# con-right-top.net
KiCad netlist of a schematic drawn in Altium Designer
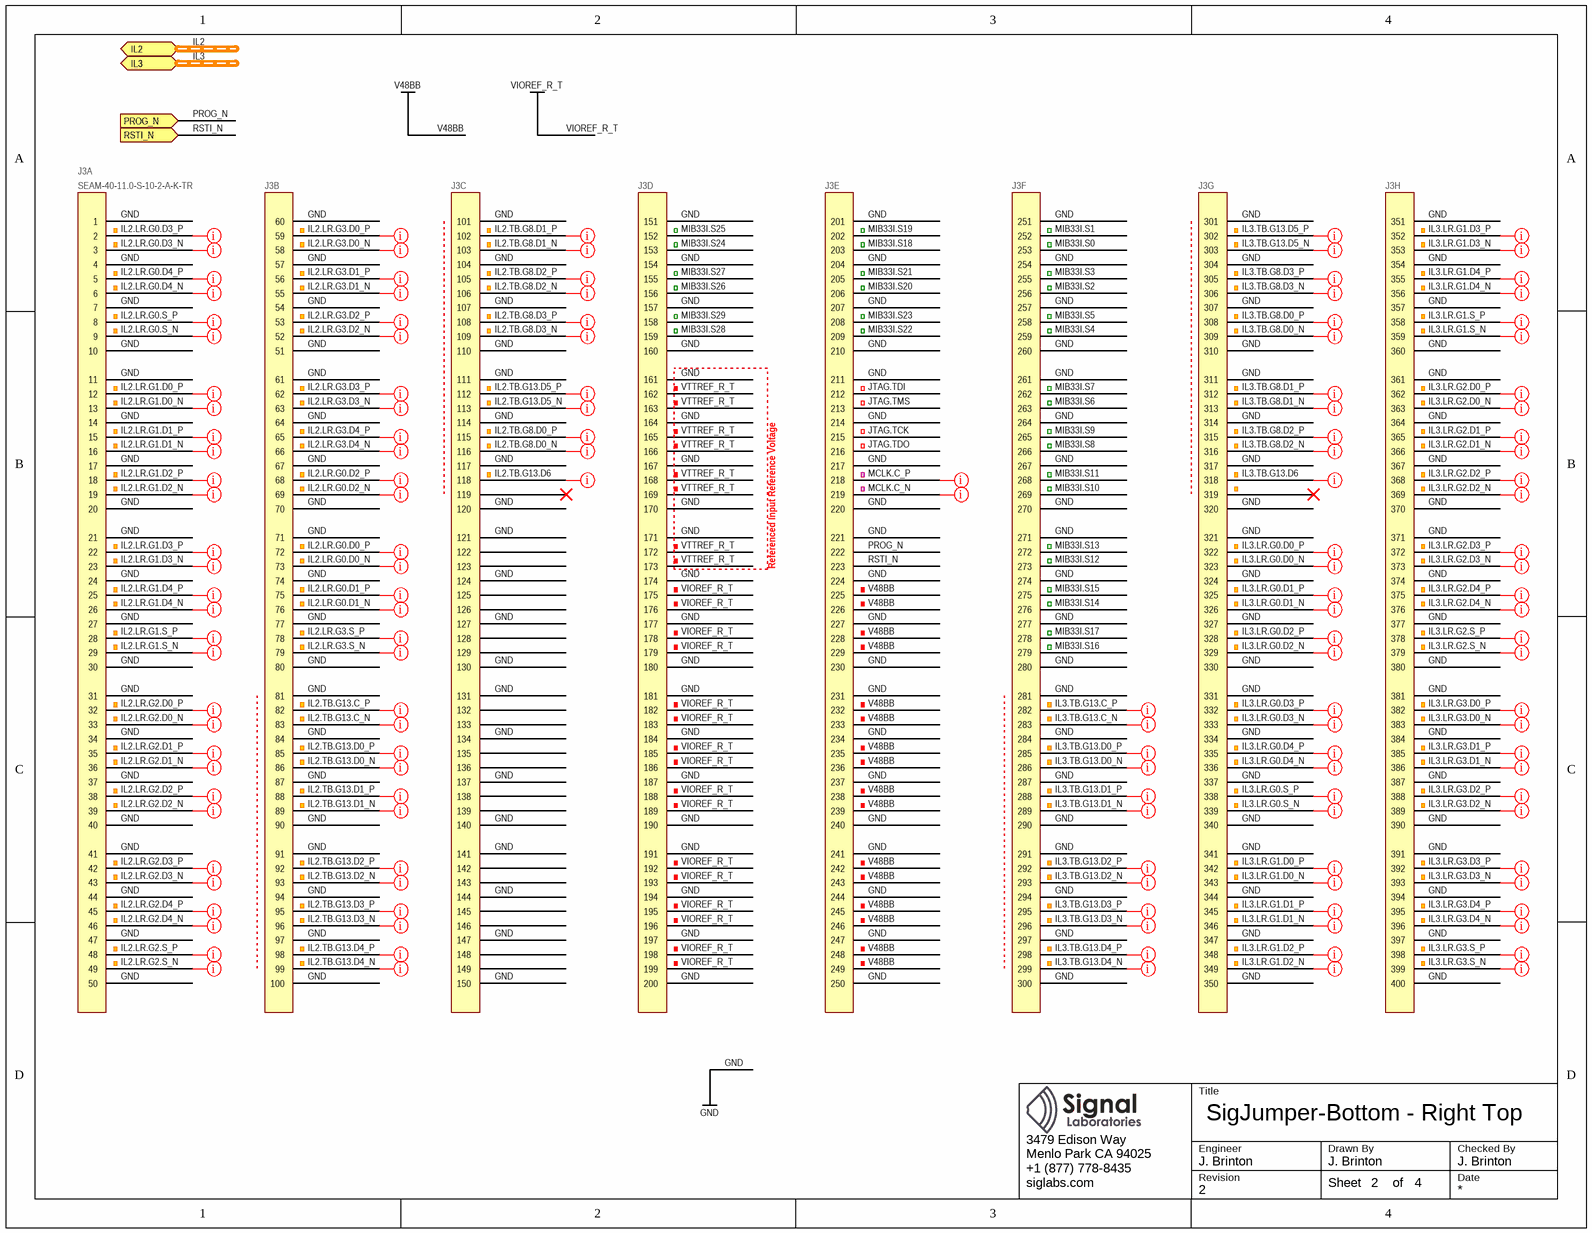
[diagram p0: con-right-top.SchDoc]

(export (version "E")
  (design (tool "Eeschema 10.0.6"))
  (components
    (comp (ref "J3")
      (value "SEAM-40-11.0-S-10-2-A-K-TR")
      (footprint "samtec:SEAM-40-11.0-S-10-2-A-K-TR")
      (description "Terminal Array Assembly, Surface Mount, 0.050\" Pitch, 400 Pins")
      (fields (field (name "MANUFACTURER") "Samtec"))
      (libsource (lib "samtec") (part "SEAM-40-11.0-S-10-2-A-K-TR"))
    )
  )
  (nets
    (net (code "3") (name "/IL2.LR.G0.D0_N") (class "Default")
      (node (ref "J3") (pin "73") (pinfunction "73_73") (pintype "passive"))
    )
    (net (code "4") (name "/IL2.LR.G0.D0_P") (class "Default")
      (node (ref "J3") (pin "72") (pinfunction "72_72") (pintype "passive"))
    )
    (net (code "5") (name "/IL2.LR.G0.D1_N") (class "Default")
      (node (ref "J3") (pin "76") (pinfunction "76_76") (pintype "passive"))
    )
    (net (code "6") (name "/IL2.LR.G0.D1_P") (class "Default")
      (node (ref "J3") (pin "75") (pinfunction "75_75") (pintype "passive"))
    )
    (net (code "7") (name "/IL2.LR.G0.D2_N") (class "Default")
      (node (ref "J3") (pin "69") (pinfunction "69_69") (pintype "passive"))
    )
    (net (code "8") (name "/IL2.LR.G0.D2_P") (class "Default")
      (node (ref "J3") (pin "68") (pinfunction "68_68") (pintype "passive"))
    )
    (net (code "9") (name "/IL2.LR.G0.D3_N") (class "Default")
      (node (ref "J3") (pin "3") (pinfunction "3_3") (pintype "passive"))
    )
    (net (code "10") (name "/IL2.LR.G0.D3_P") (class "Default")
      (node (ref "J3") (pin "2") (pinfunction "2_2") (pintype "passive"))
    )
    (net (code "11") (name "/IL2.LR.G0.D4_N") (class "Default")
      (node (ref "J3") (pin "6") (pinfunction "6_6") (pintype "passive"))
    )
    (net (code "12") (name "/IL2.LR.G0.D4_P") (class "Default")
      (node (ref "J3") (pin "5") (pinfunction "5_5") (pintype "passive"))
    )
    (net (code "13") (name "/IL2.LR.G0.S_N") (class "Default")
      (node (ref "J3") (pin "9") (pinfunction "9_9") (pintype "passive"))
    )
    (net (code "14") (name "/IL2.LR.G0.S_P") (class "Default")
      (node (ref "J3") (pin "8") (pinfunction "8_8") (pintype "passive"))
    )
    (net (code "15") (name "/IL2.LR.G1.D0_N") (class "Default")
      (node (ref "J3") (pin "13") (pinfunction "13_13") (pintype "passive"))
    )
    (net (code "16") (name "/IL2.LR.G1.D0_P") (class "Default")
      (node (ref "J3") (pin "12") (pinfunction "12_12") (pintype "passive"))
    )
    (net (code "17") (name "/IL2.LR.G1.D1_N") (class "Default")
      (node (ref "J3") (pin "16") (pinfunction "16_16") (pintype "passive"))
    )
    (net (code "18") (name "/IL2.LR.G1.D1_P") (class "Default")
      (node (ref "J3") (pin "15") (pinfunction "15_15") (pintype "passive"))
    )
    (net (code "19") (name "/IL2.LR.G1.D2_N") (class "Default")
      (node (ref "J3") (pin "19") (pinfunction "19_19") (pintype "passive"))
    )
    (net (code "20") (name "/IL2.LR.G1.D2_P") (class "Default")
      (node (ref "J3") (pin "18") (pinfunction "18_18") (pintype "passive"))
    )
    (net (code "21") (name "/IL2.LR.G1.D3_N") (class "Default")
      (node (ref "J3") (pin "23") (pinfunction "23_23") (pintype "passive"))
    )
    (net (code "22") (name "/IL2.LR.G1.D3_P") (class "Default")
      (node (ref "J3") (pin "22") (pinfunction "22_22") (pintype "passive"))
    )
    (net (code "23") (name "/IL2.LR.G1.D4_N") (class "Default")
      (node (ref "J3") (pin "26") (pinfunction "26_26") (pintype "passive"))
    )
    (net (code "24") (name "/IL2.LR.G1.D4_P") (class "Default")
      (node (ref "J3") (pin "25") (pinfunction "25_25") (pintype "passive"))
    )
    (net (code "25") (name "/IL2.LR.G1.S_N") (class "Default")
      (node (ref "J3") (pin "29") (pinfunction "29_29") (pintype "passive"))
    )
    (net (code "26") (name "/IL2.LR.G1.S_P") (class "Default")
      (node (ref "J3") (pin "28") (pinfunction "28_28") (pintype "passive"))
    )
    (net (code "27") (name "/IL2.LR.G2.D0_N") (class "Default")
      (node (ref "J3") (pin "33") (pinfunction "33_33") (pintype "passive"))
    )
    (net (code "28") (name "/IL2.LR.G2.D0_P") (class "Default")
      (node (ref "J3") (pin "32") (pinfunction "32_32") (pintype "passive"))
    )
    (net (code "29") (name "/IL2.LR.G2.D1_N") (class "Default")
      (node (ref "J3") (pin "36") (pinfunction "36_36") (pintype "passive"))
    )
    (net (code "30") (name "/IL2.LR.G2.D1_P") (class "Default")
      (node (ref "J3") (pin "35") (pinfunction "35_35") (pintype "passive"))
    )
    (net (code "31") (name "/IL2.LR.G2.D2_N") (class "Default")
      (node (ref "J3") (pin "39") (pinfunction "39_39") (pintype "passive"))
    )
    (net (code "32") (name "/IL2.LR.G2.D2_P") (class "Default")
      (node (ref "J3") (pin "38") (pinfunction "38_38") (pintype "passive"))
    )
    (net (code "33") (name "/IL2.LR.G2.D3_N") (class "Default")
      (node (ref "J3") (pin "43") (pinfunction "43_43") (pintype "passive"))
    )
    (net (code "34") (name "/IL2.LR.G2.D3_P") (class "Default")
      (node (ref "J3") (pin "42") (pinfunction "42_42") (pintype "passive"))
    )
    (net (code "35") (name "/IL2.LR.G2.D4_N") (class "Default")
      (node (ref "J3") (pin "46") (pinfunction "46_46") (pintype "passive"))
    )
    (net (code "36") (name "/IL2.LR.G2.D4_P") (class "Default")
      (node (ref "J3") (pin "45") (pinfunction "45_45") (pintype "passive"))
    )
    (net (code "37") (name "/IL2.LR.G2.S_N") (class "Default")
      (node (ref "J3") (pin "49") (pinfunction "49_49") (pintype "passive"))
    )
    (net (code "38") (name "/IL2.LR.G2.S_P") (class "Default")
      (node (ref "J3") (pin "48") (pinfunction "48_48") (pintype "passive"))
    )
    (net (code "39") (name "/IL2.LR.G3.D0_N") (class "Default")
      (node (ref "J3") (pin "58") (pinfunction "58_58") (pintype "passive"))
    )
    (net (code "40") (name "/IL2.LR.G3.D0_P") (class "Default")
      (node (ref "J3") (pin "59") (pinfunction "59_59") (pintype "passive"))
    )
    (net (code "41") (name "/IL2.LR.G3.D1_N") (class "Default")
      (node (ref "J3") (pin "55") (pinfunction "55_55") (pintype "passive"))
    )
    (net (code "42") (name "/IL2.LR.G3.D1_P") (class "Default")
      (node (ref "J3") (pin "56") (pinfunction "56_56") (pintype "passive"))
    )
    (net (code "43") (name "/IL2.LR.G3.D2_N") (class "Default")
      (node (ref "J3") (pin "52") (pinfunction "52_52") (pintype "passive"))
    )
    (net (code "44") (name "/IL2.LR.G3.D2_P") (class "Default")
      (node (ref "J3") (pin "53") (pinfunction "53_53") (pintype "passive"))
    )
    (net (code "45") (name "/IL2.LR.G3.D3_N") (class "Default")
      (node (ref "J3") (pin "63") (pinfunction "63_63") (pintype "passive"))
    )
    (net (code "46") (name "/IL2.LR.G3.D3_P") (class "Default")
      (node (ref "J3") (pin "62") (pinfunction "62_62") (pintype "passive"))
    )
    (net (code "47") (name "/IL2.LR.G3.D4_N") (class "Default")
      (node (ref "J3") (pin "66") (pinfunction "66_66") (pintype "passive"))
    )
    (net (code "48") (name "/IL2.LR.G3.D4_P") (class "Default")
      (node (ref "J3") (pin "65") (pinfunction "65_65") (pintype "passive"))
    )
    (net (code "49") (name "/IL2.LR.G3.S_N") (class "Default")
      (node (ref "J3") (pin "79") (pinfunction "79_79") (pintype "passive"))
    )
    (net (code "50") (name "/IL2.LR.G3.S_P") (class "Default")
      (node (ref "J3") (pin "78") (pinfunction "78_78") (pintype "passive"))
    )
    (net (code "51") (name "/IL2.TB.G8.D0_N") (class "Default")
      (node (ref "J3") (pin "116") (pinfunction "116_116") (pintype "passive"))
    )
    (net (code "52") (name "/IL2.TB.G8.D0_P") (class "Default")
      (node (ref "J3") (pin "115") (pinfunction "115_115") (pintype "passive"))
    )
    (net (code "53") (name "/IL2.TB.G8.D1_N") (class "Default")
      (node (ref "J3") (pin "103") (pinfunction "103_103") (pintype "passive"))
    )
    (net (code "54") (name "/IL2.TB.G8.D1_P") (class "Default")
      (node (ref "J3") (pin "102") (pinfunction "102_102") (pintype "passive"))
    )
    (net (code "55") (name "/IL2.TB.G8.D2_N") (class "Default")
      (node (ref "J3") (pin "106") (pinfunction "106_106") (pintype "passive"))
    )
    (net (code "56") (name "/IL2.TB.G8.D2_P") (class "Default")
      (node (ref "J3") (pin "105") (pinfunction "105_105") (pintype "passive"))
    )
    (net (code "57") (name "/IL2.TB.G8.D3_N") (class "Default")
      (node (ref "J3") (pin "109") (pinfunction "109_109") (pintype "passive"))
    )
    (net (code "58") (name "/IL2.TB.G8.D3_P") (class "Default")
      (node (ref "J3") (pin "108") (pinfunction "108_108") (pintype "passive"))
    )
    (net (code "59") (name "/IL2.TB.G13.C_N") (class "Default")
      (node (ref "J3") (pin "83") (pinfunction "83_83") (pintype "passive"))
    )
    (net (code "60") (name "/IL2.TB.G13.C_P") (class "Default")
      (node (ref "J3") (pin "82") (pinfunction "82_82") (pintype "passive"))
    )
    (net (code "61") (name "/IL2.TB.G13.D0_N") (class "Default")
      (node (ref "J3") (pin "86") (pinfunction "86_86") (pintype "passive"))
    )
    (net (code "62") (name "/IL2.TB.G13.D0_P") (class "Default")
      (node (ref "J3") (pin "85") (pinfunction "85_85") (pintype "passive"))
    )
    (net (code "63") (name "/IL2.TB.G13.D1_N") (class "Default")
      (node (ref "J3") (pin "89") (pinfunction "89_89") (pintype "passive"))
    )
    (net (code "64") (name "/IL2.TB.G13.D1_P") (class "Default")
      (node (ref "J3") (pin "88") (pinfunction "88_88") (pintype "passive"))
    )
    (net (code "65") (name "/IL2.TB.G13.D2_N") (class "Default")
      (node (ref "J3") (pin "93") (pinfunction "93_93") (pintype "passive"))
    )
    (net (code "66") (name "/IL2.TB.G13.D2_P") (class "Default")
      (node (ref "J3") (pin "92") (pinfunction "92_92") (pintype "passive"))
    )
    (net (code "67") (name "/IL2.TB.G13.D3_N") (class "Default")
      (node (ref "J3") (pin "96") (pinfunction "96_96") (pintype "passive"))
    )
    (net (code "68") (name "/IL2.TB.G13.D3_P") (class "Default")
      (node (ref "J3") (pin "95") (pinfunction "95_95") (pintype "passive"))
    )
    (net (code "69") (name "/IL2.TB.G13.D4_N") (class "Default")
      (node (ref "J3") (pin "99") (pinfunction "99_99") (pintype "passive"))
    )
    (net (code "70") (name "/IL2.TB.G13.D4_P") (class "Default")
      (node (ref "J3") (pin "98") (pinfunction "98_98") (pintype "passive"))
    )
    (net (code "71") (name "/IL2.TB.G13.D5_N") (class "Default")
      (node (ref "J3") (pin "113") (pinfunction "113_113") (pintype "passive"))
    )
    (net (code "72") (name "/IL2.TB.G13.D5_P") (class "Default")
      (node (ref "J3") (pin "112") (pinfunction "112_112") (pintype "passive"))
    )
    (net (code "73") (name "/IL2.TB.G13.D6") (class "Default")
      (node (ref "J3") (pin "118") (pinfunction "118_118") (pintype "passive"))
    )
    (net (code "74") (name "/IL3.LR.G0.D0_N") (class "Default")
      (node (ref "J3") (pin "323") (pinfunction "323_323") (pintype "passive"))
    )
    (net (code "75") (name "/IL3.LR.G0.D0_P") (class "Default")
      (node (ref "J3") (pin "322") (pinfunction "322_322") (pintype "passive"))
    )
    (net (code "76") (name "/IL3.LR.G0.D1_N") (class "Default")
      (node (ref "J3") (pin "326") (pinfunction "326_326") (pintype "passive"))
    )
    (net (code "77") (name "/IL3.LR.G0.D1_P") (class "Default")
      (node (ref "J3") (pin "325") (pinfunction "325_325") (pintype "passive"))
    )
    (net (code "78") (name "/IL3.LR.G0.D2_N") (class "Default")
      (node (ref "J3") (pin "329") (pinfunction "329_329") (pintype "passive"))
    )
    (net (code "79") (name "/IL3.LR.G0.D2_P") (class "Default")
      (node (ref "J3") (pin "328") (pinfunction "328_328") (pintype "passive"))
    )
    (net (code "80") (name "/IL3.LR.G0.D3_N") (class "Default")
      (node (ref "J3") (pin "333") (pinfunction "333_333") (pintype "passive"))
    )
    (net (code "81") (name "/IL3.LR.G0.D3_P") (class "Default")
      (node (ref "J3") (pin "332") (pinfunction "332_332") (pintype "passive"))
    )
    (net (code "82") (name "/IL3.LR.G0.D4_N") (class "Default")
      (node (ref "J3") (pin "336") (pinfunction "336_336") (pintype "passive"))
    )
    (net (code "83") (name "/IL3.LR.G0.D4_P") (class "Default")
      (node (ref "J3") (pin "335") (pinfunction "335_335") (pintype "passive"))
    )
    (net (code "84") (name "/IL3.LR.G0.S_N") (class "Default")
      (node (ref "J3") (pin "339") (pinfunction "339_339") (pintype "passive"))
    )
    (net (code "85") (name "/IL3.LR.G0.S_P") (class "Default")
      (node (ref "J3") (pin "338") (pinfunction "338_338") (pintype "passive"))
    )
    (net (code "86") (name "/IL3.LR.G1.D0_N") (class "Default")
      (node (ref "J3") (pin "343") (pinfunction "343_343") (pintype "passive"))
    )
    (net (code "87") (name "/IL3.LR.G1.D0_P") (class "Default")
      (node (ref "J3") (pin "342") (pinfunction "342_342") (pintype "passive"))
    )
    (net (code "88") (name "/IL3.LR.G1.D1_N") (class "Default")
      (node (ref "J3") (pin "346") (pinfunction "346_346") (pintype "passive"))
    )
    (net (code "89") (name "/IL3.LR.G1.D1_P") (class "Default")
      (node (ref "J3") (pin "345") (pinfunction "345_345") (pintype "passive"))
    )
    (net (code "90") (name "/IL3.LR.G1.D2_N") (class "Default")
      (node (ref "J3") (pin "349") (pinfunction "349_349") (pintype "passive"))
    )
    (net (code "91") (name "/IL3.LR.G1.D2_P") (class "Default")
      (node (ref "J3") (pin "348") (pinfunction "348_348") (pintype "passive"))
    )
    (net (code "92") (name "/IL3.LR.G1.D3_N") (class "Default")
      (node (ref "J3") (pin "353") (pinfunction "353_353") (pintype "passive"))
    )
    (net (code "93") (name "/IL3.LR.G1.D3_P") (class "Default")
      (node (ref "J3") (pin "352") (pinfunction "352_352") (pintype "passive"))
    )
    (net (code "94") (name "/IL3.LR.G1.D4_N") (class "Default")
      (node (ref "J3") (pin "356") (pinfunction "356_356") (pintype "passive"))
    )
    (net (code "95") (name "/IL3.LR.G1.D4_P") (class "Default")
      (node (ref "J3") (pin "355") (pinfunction "355_355") (pintype "passive"))
    )
    (net (code "96") (name "/IL3.LR.G1.S_N") (class "Default")
      (node (ref "J3") (pin "359") (pinfunction "359_359") (pintype "passive"))
    )
    (net (code "97") (name "/IL3.LR.G1.S_P") (class "Default")
      (node (ref "J3") (pin "358") (pinfunction "358_358") (pintype "passive"))
    )
    (net (code "98") (name "/IL3.LR.G2.D0_N") (class "Default")
      (node (ref "J3") (pin "363") (pinfunction "363_363") (pintype "passive"))
    )
    (net (code "99") (name "/IL3.LR.G2.D0_P") (class "Default")
      (node (ref "J3") (pin "362") (pinfunction "362_362") (pintype "passive"))
    )
    (net (code "100") (name "/IL3.LR.G2.D1_N") (class "Default")
      (node (ref "J3") (pin "366") (pinfunction "366_366") (pintype "passive"))
    )
    (net (code "101") (name "/IL3.LR.G2.D1_P") (class "Default")
      (node (ref "J3") (pin "365") (pinfunction "365_365") (pintype "passive"))
    )
    (net (code "102") (name "/IL3.LR.G2.D2_N") (class "Default")
      (node (ref "J3") (pin "369") (pinfunction "369_369") (pintype "passive"))
    )
    (net (code "103") (name "/IL3.LR.G2.D2_P") (class "Default")
      (node (ref "J3") (pin "368") (pinfunction "368_368") (pintype "passive"))
    )
    (net (code "104") (name "/IL3.LR.G2.D3_N") (class "Default")
      (node (ref "J3") (pin "373") (pinfunction "373_373") (pintype "passive"))
    )
    (net (code "105") (name "/IL3.LR.G2.D3_P") (class "Default")
      (node (ref "J3") (pin "372") (pinfunction "372_372") (pintype "passive"))
    )
    (net (code "106") (name "/IL3.LR.G2.D4_N") (class "Default")
      (node (ref "J3") (pin "376") (pinfunction "376_376") (pintype "passive"))
    )
    (net (code "107") (name "/IL3.LR.G2.D4_P") (class "Default")
      (node (ref "J3") (pin "375") (pinfunction "375_375") (pintype "passive"))
    )
    (net (code "108") (name "/IL3.LR.G2.S_N") (class "Default")
      (node (ref "J3") (pin "379") (pinfunction "379_379") (pintype "passive"))
    )
    (net (code "109") (name "/IL3.LR.G2.S_P") (class "Default")
      (node (ref "J3") (pin "378") (pinfunction "378_378") (pintype "passive"))
    )
    (net (code "110") (name "/IL3.LR.G3.D0_N") (class "Default")
      (node (ref "J3") (pin "383") (pinfunction "383_383") (pintype "passive"))
    )
    (net (code "111") (name "/IL3.LR.G3.D0_P") (class "Default")
      (node (ref "J3") (pin "382") (pinfunction "382_382") (pintype "passive"))
    )
    (net (code "112") (name "/IL3.LR.G3.D1_N") (class "Default")
      (node (ref "J3") (pin "386") (pinfunction "386_386") (pintype "passive"))
    )
    (net (code "113") (name "/IL3.LR.G3.D1_P") (class "Default")
      (node (ref "J3") (pin "385") (pinfunction "385_385") (pintype "passive"))
    )
    (net (code "114") (name "/IL3.LR.G3.D2_N") (class "Default")
      (node (ref "J3") (pin "389") (pinfunction "389_389") (pintype "passive"))
    )
    (net (code "115") (name "/IL3.LR.G3.D2_P") (class "Default")
      (node (ref "J3") (pin "388") (pinfunction "388_388") (pintype "passive"))
    )
    (net (code "116") (name "/IL3.LR.G3.D3_N") (class "Default")
      (node (ref "J3") (pin "393") (pinfunction "393_393") (pintype "passive"))
    )
    (net (code "117") (name "/IL3.LR.G3.D3_P") (class "Default")
      (node (ref "J3") (pin "392") (pinfunction "392_392") (pintype "passive"))
    )
    (net (code "118") (name "/IL3.LR.G3.D4_N") (class "Default")
      (node (ref "J3") (pin "396") (pinfunction "396_396") (pintype "passive"))
    )
    (net (code "119") (name "/IL3.LR.G3.D4_P") (class "Default")
      (node (ref "J3") (pin "395") (pinfunction "395_395") (pintype "passive"))
    )
    (net (code "120") (name "/IL3.LR.G3.S_N") (class "Default")
      (node (ref "J3") (pin "399") (pinfunction "399_399") (pintype "passive"))
    )
    (net (code "121") (name "/IL3.LR.G3.S_P") (class "Default")
      (node (ref "J3") (pin "398") (pinfunction "398_398") (pintype "passive"))
    )
    (net (code "122") (name "/IL3.TB.G8.D0_N") (class "Default")
      (node (ref "J3") (pin "309") (pinfunction "309_309") (pintype "passive"))
    )
    (net (code "123") (name "/IL3.TB.G8.D0_P") (class "Default")
      (node (ref "J3") (pin "308") (pinfunction "308_308") (pintype "passive"))
    )
    (net (code "124") (name "/IL3.TB.G8.D1_N") (class "Default")
      (node (ref "J3") (pin "313") (pinfunction "313_313") (pintype "passive"))
    )
    (net (code "125") (name "/IL3.TB.G8.D1_P") (class "Default")
      (node (ref "J3") (pin "312") (pinfunction "312_312") (pintype "passive"))
    )
    (net (code "126") (name "/IL3.TB.G8.D2_N") (class "Default")
      (node (ref "J3") (pin "316") (pinfunction "316_316") (pintype "passive"))
    )
    (net (code "127") (name "/IL3.TB.G8.D2_P") (class "Default")
      (node (ref "J3") (pin "315") (pinfunction "315_315") (pintype "passive"))
    )
    (net (code "128") (name "/IL3.TB.G8.D3_N") (class "Default")
      (node (ref "J3") (pin "306") (pinfunction "306_306") (pintype "passive"))
    )
    (net (code "129") (name "/IL3.TB.G8.D3_P") (class "Default")
      (node (ref "J3") (pin "305") (pinfunction "305_305") (pintype "passive"))
    )
    (net (code "130") (name "/IL3.TB.G13.C_N") (class "Default")
      (node (ref "J3") (pin "283") (pinfunction "283_283") (pintype "passive"))
    )
    (net (code "131") (name "/IL3.TB.G13.C_P") (class "Default")
      (node (ref "J3") (pin "282") (pinfunction "282_282") (pintype "passive"))
    )
    (net (code "132") (name "/IL3.TB.G13.D0_N") (class "Default")
      (node (ref "J3") (pin "286") (pinfunction "286_286") (pintype "passive"))
    )
    (net (code "133") (name "/IL3.TB.G13.D0_P") (class "Default")
      (node (ref "J3") (pin "285") (pinfunction "285_285") (pintype "passive"))
    )
    (net (code "134") (name "/IL3.TB.G13.D1_N") (class "Default")
      (node (ref "J3") (pin "289") (pinfunction "289_289") (pintype "passive"))
    )
    (net (code "135") (name "/IL3.TB.G13.D1_P") (class "Default")
      (node (ref "J3") (pin "288") (pinfunction "288_288") (pintype "passive"))
    )
    (net (code "136") (name "/IL3.TB.G13.D2_N") (class "Default")
      (node (ref "J3") (pin "293") (pinfunction "293_293") (pintype "passive"))
    )
    (net (code "137") (name "/IL3.TB.G13.D2_P") (class "Default")
      (node (ref "J3") (pin "292") (pinfunction "292_292") (pintype "passive"))
    )
    (net (code "138") (name "/IL3.TB.G13.D3_N") (class "Default")
      (node (ref "J3") (pin "296") (pinfunction "296_296") (pintype "passive"))
    )
    (net (code "139") (name "/IL3.TB.G13.D3_P") (class "Default")
      (node (ref "J3") (pin "295") (pinfunction "295_295") (pintype "passive"))
    )
    (net (code "140") (name "/IL3.TB.G13.D4_N") (class "Default")
      (node (ref "J3") (pin "299") (pinfunction "299_299") (pintype "passive"))
    )
    (net (code "141") (name "/IL3.TB.G13.D4_P") (class "Default")
      (node (ref "J3") (pin "298") (pinfunction "298_298") (pintype "passive"))
    )
    (net (code "142") (name "/IL3.TB.G13.D5_N") (class "Default")
      (node (ref "J3") (pin "303") (pinfunction "303_303") (pintype "passive"))
    )
    (net (code "143") (name "/IL3.TB.G13.D5_P") (class "Default")
      (node (ref "J3") (pin "302") (pinfunction "302_302") (pintype "passive"))
    )
    (net (code "144") (name "/IL3.TB.G13.D6") (class "Default")
      (node (ref "J3") (pin "318") (pinfunction "318_318") (pintype "passive"))
    )
    (net (code "145") (name "/JTAG.TCK") (class "Default")
      (node (ref "J3") (pin "215") (pinfunction "215_215") (pintype "passive"))
    )
    (net (code "146") (name "/JTAG.TDI") (class "Default")
      (node (ref "J3") (pin "212") (pinfunction "212_212") (pintype "passive"))
    )
    (net (code "147") (name "/JTAG.TDO") (class "Default")
      (node (ref "J3") (pin "216") (pinfunction "216_216") (pintype "passive"))
    )
    (net (code "148") (name "/JTAG.TMS") (class "Default")
      (node (ref "J3") (pin "213") (pinfunction "213_213") (pintype "passive"))
    )
    (net (code "149") (name "/MCLK.C_N") (class "Default")
      (node (ref "J3") (pin "219") (pinfunction "219_219") (pintype "passive"))
    )
    (net (code "150") (name "/MCLK.C_P") (class "Default")
      (node (ref "J3") (pin "218") (pinfunction "218_218") (pintype "passive"))
    )
    (net (code "151") (name "/MIB33I.S0") (class "Default")
      (node (ref "J3") (pin "253") (pinfunction "253_253") (pintype "passive"))
    )
    (net (code "152") (name "/MIB33I.S1") (class "Default")
      (node (ref "J3") (pin "252") (pinfunction "252_252") (pintype "passive"))
    )
    (net (code "153") (name "/MIB33I.S2") (class "Default")
      (node (ref "J3") (pin "256") (pinfunction "256_256") (pintype "passive"))
    )
    (net (code "154") (name "/MIB33I.S3") (class "Default")
      (node (ref "J3") (pin "255") (pinfunction "255_255") (pintype "passive"))
    )
    (net (code "155") (name "/MIB33I.S4") (class "Default")
      (node (ref "J3") (pin "259") (pinfunction "259_259") (pintype "passive"))
    )
    (net (code "156") (name "/MIB33I.S5") (class "Default")
      (node (ref "J3") (pin "258") (pinfunction "258_258") (pintype "passive"))
    )
    (net (code "157") (name "/MIB33I.S6") (class "Default")
      (node (ref "J3") (pin "263") (pinfunction "263_263") (pintype "passive"))
    )
    (net (code "158") (name "/MIB33I.S7") (class "Default")
      (node (ref "J3") (pin "262") (pinfunction "262_262") (pintype "passive"))
    )
    (net (code "159") (name "/MIB33I.S8") (class "Default")
      (node (ref "J3") (pin "266") (pinfunction "266_266") (pintype "passive"))
    )
    (net (code "160") (name "/MIB33I.S9") (class "Default")
      (node (ref "J3") (pin "265") (pinfunction "265_265") (pintype "passive"))
    )
    (net (code "161") (name "/MIB33I.S10") (class "Default")
      (node (ref "J3") (pin "269") (pinfunction "269_269") (pintype "passive"))
    )
    (net (code "162") (name "/MIB33I.S11") (class "Default")
      (node (ref "J3") (pin "268") (pinfunction "268_268") (pintype "passive"))
    )
    (net (code "163") (name "/MIB33I.S12") (class "Default")
      (node (ref "J3") (pin "273") (pinfunction "273_273") (pintype "passive"))
    )
    (net (code "164") (name "/MIB33I.S13") (class "Default")
      (node (ref "J3") (pin "272") (pinfunction "272_272") (pintype "passive"))
    )
    (net (code "165") (name "/MIB33I.S14") (class "Default")
      (node (ref "J3") (pin "276") (pinfunction "276_276") (pintype "passive"))
    )
    (net (code "166") (name "/MIB33I.S15") (class "Default")
      (node (ref "J3") (pin "275") (pinfunction "275_275") (pintype "passive"))
    )
    (net (code "167") (name "/MIB33I.S16") (class "Default")
      (node (ref "J3") (pin "279") (pinfunction "279_279") (pintype "passive"))
    )
    (net (code "168") (name "/MIB33I.S17") (class "Default")
      (node (ref "J3") (pin "278") (pinfunction "278_278") (pintype "passive"))
    )
    (net (code "169") (name "/MIB33I.S18") (class "Default")
      (node (ref "J3") (pin "203") (pinfunction "203_203") (pintype "passive"))
    )
    (net (code "170") (name "/MIB33I.S19") (class "Default")
      (node (ref "J3") (pin "202") (pinfunction "202_202") (pintype "passive"))
    )
    (net (code "171") (name "/MIB33I.S20") (class "Default")
      (node (ref "J3") (pin "206") (pinfunction "206_206") (pintype "passive"))
    )
    (net (code "172") (name "/MIB33I.S21") (class "Default")
      (node (ref "J3") (pin "205") (pinfunction "205_205") (pintype "passive"))
    )
    (net (code "173") (name "/MIB33I.S22") (class "Default")
      (node (ref "J3") (pin "209") (pinfunction "209_209") (pintype "passive"))
    )
    (net (code "174") (name "/MIB33I.S23") (class "Default")
      (node (ref "J3") (pin "208") (pinfunction "208_208") (pintype "passive"))
    )
    (net (code "175") (name "/MIB33I.S24") (class "Default")
      (node (ref "J3") (pin "153") (pinfunction "153_153") (pintype "passive"))
    )
    (net (code "176") (name "/MIB33I.S25") (class "Default")
      (node (ref "J3") (pin "152") (pinfunction "152_152") (pintype "passive"))
    )
    (net (code "177") (name "/MIB33I.S26") (class "Default")
      (node (ref "J3") (pin "156") (pinfunction "156_156") (pintype "passive"))
    )
    (net (code "178") (name "/MIB33I.S27") (class "Default")
      (node (ref "J3") (pin "155") (pinfunction "155_155") (pintype "passive"))
    )
    (net (code "179") (name "/MIB33I.S28") (class "Default")
      (node (ref "J3") (pin "159") (pinfunction "159_159") (pintype "passive"))
    )
    (net (code "180") (name "/MIB33I.S29") (class "Default")
      (node (ref "J3") (pin "158") (pinfunction "158_158") (pintype "passive"))
    )
    (net (code "181") (name "/PROG_N") (class "Default")
      (node (ref "J3") (pin "222") (pinfunction "222_222") (pintype "passive"))
    )
    (net (code "182") (name "/RSTI_N") (class "Default")
      (node (ref "J3") (pin "223") (pinfunction "223_223") (pintype "passive"))
    )
    (net (code "183") (name "/VTTREF_R_T") (class "Default")
      (node (ref "J3") (pin "162") (pinfunction "162_162") (pintype "passive"))
      (node (ref "J3") (pin "163") (pinfunction "163_163") (pintype "passive"))
      (node (ref "J3") (pin "165") (pinfunction "165_165") (pintype "passive"))
      (node (ref "J3") (pin "166") (pinfunction "166_166") (pintype "passive"))
      (node (ref "J3") (pin "168") (pinfunction "168_168") (pintype "passive"))
      (node (ref "J3") (pin "169") (pinfunction "169_169") (pintype "passive"))
      (node (ref "J3") (pin "172") (pinfunction "172_172") (pintype "passive"))
      (node (ref "J3") (pin "173") (pinfunction "173_173") (pintype "passive"))
    )
    (net (code "186") (name "GND") (class "Default")
      (node (ref "J3") (pin "1") (pinfunction "1_1") (pintype "passive"))
      (node (ref "J3") (pin "10") (pinfunction "10_10") (pintype "passive"))
      (node (ref "J3") (pin "100") (pinfunction "100_100") (pintype "passive"))
      (node (ref "J3") (pin "101") (pinfunction "101_101") (pintype "passive"))
      (node (ref "J3") (pin "104") (pinfunction "104_104") (pintype "passive"))
      (node (ref "J3") (pin "107") (pinfunction "107_107") (pintype "passive"))
      (node (ref "J3") (pin "11") (pinfunction "11_11") (pintype "passive"))
      (node (ref "J3") (pin "110") (pinfunction "110_110") (pintype "passive"))
      (node (ref "J3") (pin "111") (pinfunction "111_111") (pintype "passive"))
      (node (ref "J3") (pin "114") (pinfunction "114_114") (pintype "passive"))
      (node (ref "J3") (pin "117") (pinfunction "117_117") (pintype "passive"))
      (node (ref "J3") (pin "120") (pinfunction "120_120") (pintype "passive"))
      (node (ref "J3") (pin "121") (pinfunction "121_121") (pintype "passive"))
      (node (ref "J3") (pin "124") (pinfunction "124_124") (pintype "passive"))
      (node (ref "J3") (pin "127") (pinfunction "127_127") (pintype "passive"))
      (node (ref "J3") (pin "130") (pinfunction "130_130") (pintype "passive"))
      (node (ref "J3") (pin "131") (pinfunction "131_131") (pintype "passive"))
      (node (ref "J3") (pin "134") (pinfunction "134_134") (pintype "passive"))
      (node (ref "J3") (pin "137") (pinfunction "137_137") (pintype "passive"))
      (node (ref "J3") (pin "14") (pinfunction "14_14") (pintype "passive"))
      (node (ref "J3") (pin "140") (pinfunction "140_140") (pintype "passive"))
      (node (ref "J3") (pin "141") (pinfunction "141_141") (pintype "passive"))
      (node (ref "J3") (pin "144") (pinfunction "144_144") (pintype "passive"))
      (node (ref "J3") (pin "147") (pinfunction "147_147") (pintype "passive"))
      (node (ref "J3") (pin "150") (pinfunction "150_150") (pintype "passive"))
      (node (ref "J3") (pin "151") (pinfunction "151_151") (pintype "passive"))
      (node (ref "J3") (pin "154") (pinfunction "154_154") (pintype "passive"))
      (node (ref "J3") (pin "157") (pinfunction "157_157") (pintype "passive"))
      (node (ref "J3") (pin "160") (pinfunction "160_160") (pintype "passive"))
      (node (ref "J3") (pin "161") (pinfunction "161_161") (pintype "passive"))
      (node (ref "J3") (pin "164") (pinfunction "164_164") (pintype "passive"))
      (node (ref "J3") (pin "167") (pinfunction "167_167") (pintype "passive"))
      (node (ref "J3") (pin "17") (pinfunction "17_17") (pintype "passive"))
      (node (ref "J3") (pin "170") (pinfunction "170_170") (pintype "passive"))
      (node (ref "J3") (pin "171") (pinfunction "171_171") (pintype "passive"))
      (node (ref "J3") (pin "174") (pinfunction "174_174") (pintype "passive"))
      (node (ref "J3") (pin "177") (pinfunction "177_177") (pintype "passive"))
      (node (ref "J3") (pin "180") (pinfunction "180_180") (pintype "passive"))
      (node (ref "J3") (pin "181") (pinfunction "181_181") (pintype "passive"))
      (node (ref "J3") (pin "184") (pinfunction "184_184") (pintype "passive"))
      (node (ref "J3") (pin "187") (pinfunction "187_187") (pintype "passive"))
      (node (ref "J3") (pin "190") (pinfunction "190_190") (pintype "passive"))
      (node (ref "J3") (pin "191") (pinfunction "191_191") (pintype "passive"))
      (node (ref "J3") (pin "194") (pinfunction "194_194") (pintype "passive"))
      (node (ref "J3") (pin "197") (pinfunction "197_197") (pintype "passive"))
      (node (ref "J3") (pin "20") (pinfunction "20_20") (pintype "passive"))
      (node (ref "J3") (pin "200") (pinfunction "200_200") (pintype "passive"))
      (node (ref "J3") (pin "201") (pinfunction "201_201") (pintype "passive"))
      (node (ref "J3") (pin "204") (pinfunction "204_204") (pintype "passive"))
      (node (ref "J3") (pin "207") (pinfunction "207_207") (pintype "passive"))
      (node (ref "J3") (pin "21") (pinfunction "21_21") (pintype "passive"))
      (node (ref "J3") (pin "210") (pinfunction "210_210") (pintype "passive"))
      (node (ref "J3") (pin "211") (pinfunction "211_211") (pintype "passive"))
      (node (ref "J3") (pin "214") (pinfunction "214_214") (pintype "passive"))
      (node (ref "J3") (pin "217") (pinfunction "217_217") (pintype "passive"))
      (node (ref "J3") (pin "220") (pinfunction "220_220") (pintype "passive"))
      (node (ref "J3") (pin "221") (pinfunction "221_221") (pintype "passive"))
      (node (ref "J3") (pin "224") (pinfunction "224_224") (pintype "passive"))
      (node (ref "J3") (pin "227") (pinfunction "227_227") (pintype "passive"))
      (node (ref "J3") (pin "230") (pinfunction "230_230") (pintype "passive"))
      (node (ref "J3") (pin "231") (pinfunction "231_231") (pintype "passive"))
      (node (ref "J3") (pin "234") (pinfunction "234_234") (pintype "passive"))
      (node (ref "J3") (pin "237") (pinfunction "237_237") (pintype "passive"))
      (node (ref "J3") (pin "24") (pinfunction "24_24") (pintype "passive"))
      (node (ref "J3") (pin "240") (pinfunction "240_240") (pintype "passive"))
      (node (ref "J3") (pin "241") (pinfunction "241_241") (pintype "passive"))
      (node (ref "J3") (pin "244") (pinfunction "244_244") (pintype "passive"))
      (node (ref "J3") (pin "247") (pinfunction "247_247") (pintype "passive"))
      (node (ref "J3") (pin "250") (pinfunction "250_250") (pintype "passive"))
      (node (ref "J3") (pin "251") (pinfunction "251_251") (pintype "passive"))
      (node (ref "J3") (pin "254") (pinfunction "254_254") (pintype "passive"))
      (node (ref "J3") (pin "257") (pinfunction "257_257") (pintype "passive"))
      (node (ref "J3") (pin "260") (pinfunction "260_260") (pintype "passive"))
      (node (ref "J3") (pin "261") (pinfunction "261_261") (pintype "passive"))
      (node (ref "J3") (pin "264") (pinfunction "264_264") (pintype "passive"))
      (node (ref "J3") (pin "267") (pinfunction "267_267") (pintype "passive"))
      (node (ref "J3") (pin "27") (pinfunction "27_27") (pintype "passive"))
      (node (ref "J3") (pin "270") (pinfunction "270_270") (pintype "passive"))
      (node (ref "J3") (pin "271") (pinfunction "271_271") (pintype "passive"))
      (node (ref "J3") (pin "274") (pinfunction "274_274") (pintype "passive"))
      (node (ref "J3") (pin "277") (pinfunction "277_277") (pintype "passive"))
      (node (ref "J3") (pin "280") (pinfunction "280_280") (pintype "passive"))
      (node (ref "J3") (pin "281") (pinfunction "281_281") (pintype "passive"))
      (node (ref "J3") (pin "284") (pinfunction "284_284") (pintype "passive"))
      (node (ref "J3") (pin "287") (pinfunction "287_287") (pintype "passive"))
      (node (ref "J3") (pin "290") (pinfunction "290_290") (pintype "passive"))
      (node (ref "J3") (pin "291") (pinfunction "291_291") (pintype "passive"))
      (node (ref "J3") (pin "294") (pinfunction "294_294") (pintype "passive"))
      (node (ref "J3") (pin "297") (pinfunction "297_297") (pintype "passive"))
      (node (ref "J3") (pin "30") (pinfunction "30_30") (pintype "passive"))
      (node (ref "J3") (pin "300") (pinfunction "300_300") (pintype "passive"))
      (node (ref "J3") (pin "301") (pinfunction "301_301") (pintype "passive"))
      (node (ref "J3") (pin "304") (pinfunction "304_304") (pintype "passive"))
      (node (ref "J3") (pin "307") (pinfunction "307_307") (pintype "passive"))
      (node (ref "J3") (pin "31") (pinfunction "31_31") (pintype "passive"))
      (node (ref "J3") (pin "310") (pinfunction "310_310") (pintype "passive"))
      (node (ref "J3") (pin "311") (pinfunction "311_311") (pintype "passive"))
      (node (ref "J3") (pin "314") (pinfunction "314_314") (pintype "passive"))
      (node (ref "J3") (pin "317") (pinfunction "317_317") (pintype "passive"))
      (node (ref "J3") (pin "320") (pinfunction "320_320") (pintype "passive"))
      (node (ref "J3") (pin "321") (pinfunction "321_321") (pintype "passive"))
      (node (ref "J3") (pin "324") (pinfunction "324_324") (pintype "passive"))
      (node (ref "J3") (pin "327") (pinfunction "327_327") (pintype "passive"))
      (node (ref "J3") (pin "330") (pinfunction "330_330") (pintype "passive"))
      (node (ref "J3") (pin "331") (pinfunction "331_331") (pintype "passive"))
      (node (ref "J3") (pin "334") (pinfunction "334_334") (pintype "passive"))
      (node (ref "J3") (pin "337") (pinfunction "337_337") (pintype "passive"))
      (node (ref "J3") (pin "34") (pinfunction "34_34") (pintype "passive"))
      (node (ref "J3") (pin "340") (pinfunction "340_340") (pintype "passive"))
      (node (ref "J3") (pin "341") (pinfunction "341_341") (pintype "passive"))
      (node (ref "J3") (pin "344") (pinfunction "344_344") (pintype "passive"))
      (node (ref "J3") (pin "347") (pinfunction "347_347") (pintype "passive"))
      (node (ref "J3") (pin "350") (pinfunction "350_350") (pintype "passive"))
      (node (ref "J3") (pin "351") (pinfunction "351_351") (pintype "passive"))
      (node (ref "J3") (pin "354") (pinfunction "354_354") (pintype "passive"))
      (node (ref "J3") (pin "357") (pinfunction "357_357") (pintype "passive"))
      (node (ref "J3") (pin "360") (pinfunction "360_360") (pintype "passive"))
      (node (ref "J3") (pin "361") (pinfunction "361_361") (pintype "passive"))
      (node (ref "J3") (pin "364") (pinfunction "364_364") (pintype "passive"))
      (node (ref "J3") (pin "367") (pinfunction "367_367") (pintype "passive"))
      (node (ref "J3") (pin "37") (pinfunction "37_37") (pintype "passive"))
      (node (ref "J3") (pin "370") (pinfunction "370_370") (pintype "passive"))
      (node (ref "J3") (pin "371") (pinfunction "371_371") (pintype "passive"))
      (node (ref "J3") (pin "374") (pinfunction "374_374") (pintype "passive"))
      (node (ref "J3") (pin "377") (pinfunction "377_377") (pintype "passive"))
      (node (ref "J3") (pin "380") (pinfunction "380_380") (pintype "passive"))
      (node (ref "J3") (pin "381") (pinfunction "381_381") (pintype "passive"))
      (node (ref "J3") (pin "384") (pinfunction "384_384") (pintype "passive"))
      (node (ref "J3") (pin "387") (pinfunction "387_387") (pintype "passive"))
      (node (ref "J3") (pin "390") (pinfunction "390_390") (pintype "passive"))
      (node (ref "J3") (pin "391") (pinfunction "391_391") (pintype "passive"))
      (node (ref "J3") (pin "394") (pinfunction "394_394") (pintype "passive"))
      (node (ref "J3") (pin "397") (pinfunction "397_397") (pintype "passive"))
      (node (ref "J3") (pin "4") (pinfunction "4_4") (pintype "passive"))
      (node (ref "J3") (pin "40") (pinfunction "40_40") (pintype "passive"))
      (node (ref "J3") (pin "400") (pinfunction "400_400") (pintype "passive"))
      (node (ref "J3") (pin "41") (pinfunction "41_41") (pintype "passive"))
      (node (ref "J3") (pin "44") (pinfunction "44_44") (pintype "passive"))
      (node (ref "J3") (pin "47") (pinfunction "47_47") (pintype "passive"))
      (node (ref "J3") (pin "50") (pinfunction "50_50") (pintype "passive"))
      (node (ref "J3") (pin "51") (pinfunction "51_51") (pintype "passive"))
      (node (ref "J3") (pin "54") (pinfunction "54_54") (pintype "passive"))
      (node (ref "J3") (pin "57") (pinfunction "57_57") (pintype "passive"))
      (node (ref "J3") (pin "60") (pinfunction "60_60") (pintype "passive"))
      (node (ref "J3") (pin "61") (pinfunction "61_61") (pintype "passive"))
      (node (ref "J3") (pin "64") (pinfunction "64_64") (pintype "passive"))
      (node (ref "J3") (pin "67") (pinfunction "67_67") (pintype "passive"))
      (node (ref "J3") (pin "7") (pinfunction "7_7") (pintype "passive"))
      (node (ref "J3") (pin "70") (pinfunction "70_70") (pintype "passive"))
      (node (ref "J3") (pin "71") (pinfunction "71_71") (pintype "passive"))
      (node (ref "J3") (pin "74") (pinfunction "74_74") (pintype "passive"))
      (node (ref "J3") (pin "77") (pinfunction "77_77") (pintype "passive"))
      (node (ref "J3") (pin "80") (pinfunction "80_80") (pintype "passive"))
      (node (ref "J3") (pin "81") (pinfunction "81_81") (pintype "passive"))
      (node (ref "J3") (pin "84") (pinfunction "84_84") (pintype "passive"))
      (node (ref "J3") (pin "87") (pinfunction "87_87") (pintype "passive"))
      (node (ref "J3") (pin "90") (pinfunction "90_90") (pintype "passive"))
      (node (ref "J3") (pin "91") (pinfunction "91_91") (pintype "passive"))
      (node (ref "J3") (pin "94") (pinfunction "94_94") (pintype "passive"))
      (node (ref "J3") (pin "97") (pinfunction "97_97") (pintype "passive"))
    )
    (net (code "187") (name "V48BB") (class "Default")
      (node (ref "J3") (pin "225") (pinfunction "225_225") (pintype "passive"))
      (node (ref "J3") (pin "226") (pinfunction "226_226") (pintype "passive"))
      (node (ref "J3") (pin "228") (pinfunction "228_228") (pintype "passive"))
      (node (ref "J3") (pin "229") (pinfunction "229_229") (pintype "passive"))
      (node (ref "J3") (pin "232") (pinfunction "232_232") (pintype "passive"))
      (node (ref "J3") (pin "233") (pinfunction "233_233") (pintype "passive"))
      (node (ref "J3") (pin "235") (pinfunction "235_235") (pintype "passive"))
      (node (ref "J3") (pin "236") (pinfunction "236_236") (pintype "passive"))
      (node (ref "J3") (pin "238") (pinfunction "238_238") (pintype "passive"))
      (node (ref "J3") (pin "239") (pinfunction "239_239") (pintype "passive"))
      (node (ref "J3") (pin "242") (pinfunction "242_242") (pintype "passive"))
      (node (ref "J3") (pin "243") (pinfunction "243_243") (pintype "passive"))
      (node (ref "J3") (pin "245") (pinfunction "245_245") (pintype "passive"))
      (node (ref "J3") (pin "246") (pinfunction "246_246") (pintype "passive"))
      (node (ref "J3") (pin "248") (pinfunction "248_248") (pintype "passive"))
      (node (ref "J3") (pin "249") (pinfunction "249_249") (pintype "passive"))
    )
    (net (code "188") (name "VIOREF_R_T") (class "Default")
      (node (ref "J3") (pin "175") (pinfunction "175_175") (pintype "passive"))
      (node (ref "J3") (pin "176") (pinfunction "176_176") (pintype "passive"))
      (node (ref "J3") (pin "178") (pinfunction "178_178") (pintype "passive"))
      (node (ref "J3") (pin "179") (pinfunction "179_179") (pintype "passive"))
      (node (ref "J3") (pin "182") (pinfunction "182_182") (pintype "passive"))
      (node (ref "J3") (pin "183") (pinfunction "183_183") (pintype "passive"))
      (node (ref "J3") (pin "185") (pinfunction "185_185") (pintype "passive"))
      (node (ref "J3") (pin "186") (pinfunction "186_186") (pintype "passive"))
      (node (ref "J3") (pin "188") (pinfunction "188_188") (pintype "passive"))
      (node (ref "J3") (pin "189") (pinfunction "189_189") (pintype "passive"))
      (node (ref "J3") (pin "192") (pinfunction "192_192") (pintype "passive"))
      (node (ref "J3") (pin "193") (pinfunction "193_193") (pintype "passive"))
      (node (ref "J3") (pin "195") (pinfunction "195_195") (pintype "passive"))
      (node (ref "J3") (pin "196") (pinfunction "196_196") (pintype "passive"))
      (node (ref "J3") (pin "198") (pinfunction "198_198") (pintype "passive"))
      (node (ref "J3") (pin "199") (pinfunction "199_199") (pintype "passive"))
    )
    (net (code "189") (name "unconnected-(J3-Pad119)") (class "Default")
      (node (ref "J3") (pin "119") (pinfunction "119_119") (pintype "passive+no_connect"))
    )
    (net (code "190") (name "unconnected-(J3-Pad122)") (class "Default")
      (node (ref "J3") (pin "122") (pinfunction "122_122") (pintype "passive"))
    )
    (net (code "191") (name "unconnected-(J3-Pad123)") (class "Default")
      (node (ref "J3") (pin "123") (pinfunction "123_123") (pintype "passive"))
    )
    (net (code "192") (name "unconnected-(J3-Pad125)") (class "Default")
      (node (ref "J3") (pin "125") (pinfunction "125_125") (pintype "passive"))
    )
    (net (code "193") (name "unconnected-(J3-Pad126)") (class "Default")
      (node (ref "J3") (pin "126") (pinfunction "126_126") (pintype "passive"))
    )
    (net (code "194") (name "unconnected-(J3-Pad128)") (class "Default")
      (node (ref "J3") (pin "128") (pinfunction "128_128") (pintype "passive"))
    )
    (net (code "195") (name "unconnected-(J3-Pad129)") (class "Default")
      (node (ref "J3") (pin "129") (pinfunction "129_129") (pintype "passive"))
    )
    (net (code "196") (name "unconnected-(J3-Pad132)") (class "Default")
      (node (ref "J3") (pin "132") (pinfunction "132_132") (pintype "passive"))
    )
    (net (code "197") (name "unconnected-(J3-Pad133)") (class "Default")
      (node (ref "J3") (pin "133") (pinfunction "133_133") (pintype "passive"))
    )
    (net (code "198") (name "unconnected-(J3-Pad135)") (class "Default")
      (node (ref "J3") (pin "135") (pinfunction "135_135") (pintype "passive"))
    )
    (net (code "199") (name "unconnected-(J3-Pad136)") (class "Default")
      (node (ref "J3") (pin "136") (pinfunction "136_136") (pintype "passive"))
    )
    (net (code "200") (name "unconnected-(J3-Pad138)") (class "Default")
      (node (ref "J3") (pin "138") (pinfunction "138_138") (pintype "passive"))
    )
    (net (code "201") (name "unconnected-(J3-Pad139)") (class "Default")
      (node (ref "J3") (pin "139") (pinfunction "139_139") (pintype "passive"))
    )
    (net (code "202") (name "unconnected-(J3-Pad142)") (class "Default")
      (node (ref "J3") (pin "142") (pinfunction "142_142") (pintype "passive"))
    )
    (net (code "203") (name "unconnected-(J3-Pad143)") (class "Default")
      (node (ref "J3") (pin "143") (pinfunction "143_143") (pintype "passive"))
    )
    (net (code "204") (name "unconnected-(J3-Pad145)") (class "Default")
      (node (ref "J3") (pin "145") (pinfunction "145_145") (pintype "passive"))
    )
    (net (code "205") (name "unconnected-(J3-Pad146)") (class "Default")
      (node (ref "J3") (pin "146") (pinfunction "146_146") (pintype "passive"))
    )
    (net (code "206") (name "unconnected-(J3-Pad148)") (class "Default")
      (node (ref "J3") (pin "148") (pinfunction "148_148") (pintype "passive"))
    )
    (net (code "207") (name "unconnected-(J3-Pad149)") (class "Default")
      (node (ref "J3") (pin "149") (pinfunction "149_149") (pintype "passive"))
    )
    (net (code "208") (name "unconnected-(J3-Pad319)") (class "Default")
      (node (ref "J3") (pin "319") (pinfunction "319_319") (pintype "passive+no_connect"))
    )
  )
)
